# AFE.net
KiCad netlist of a schematic drawn in Altium Designer
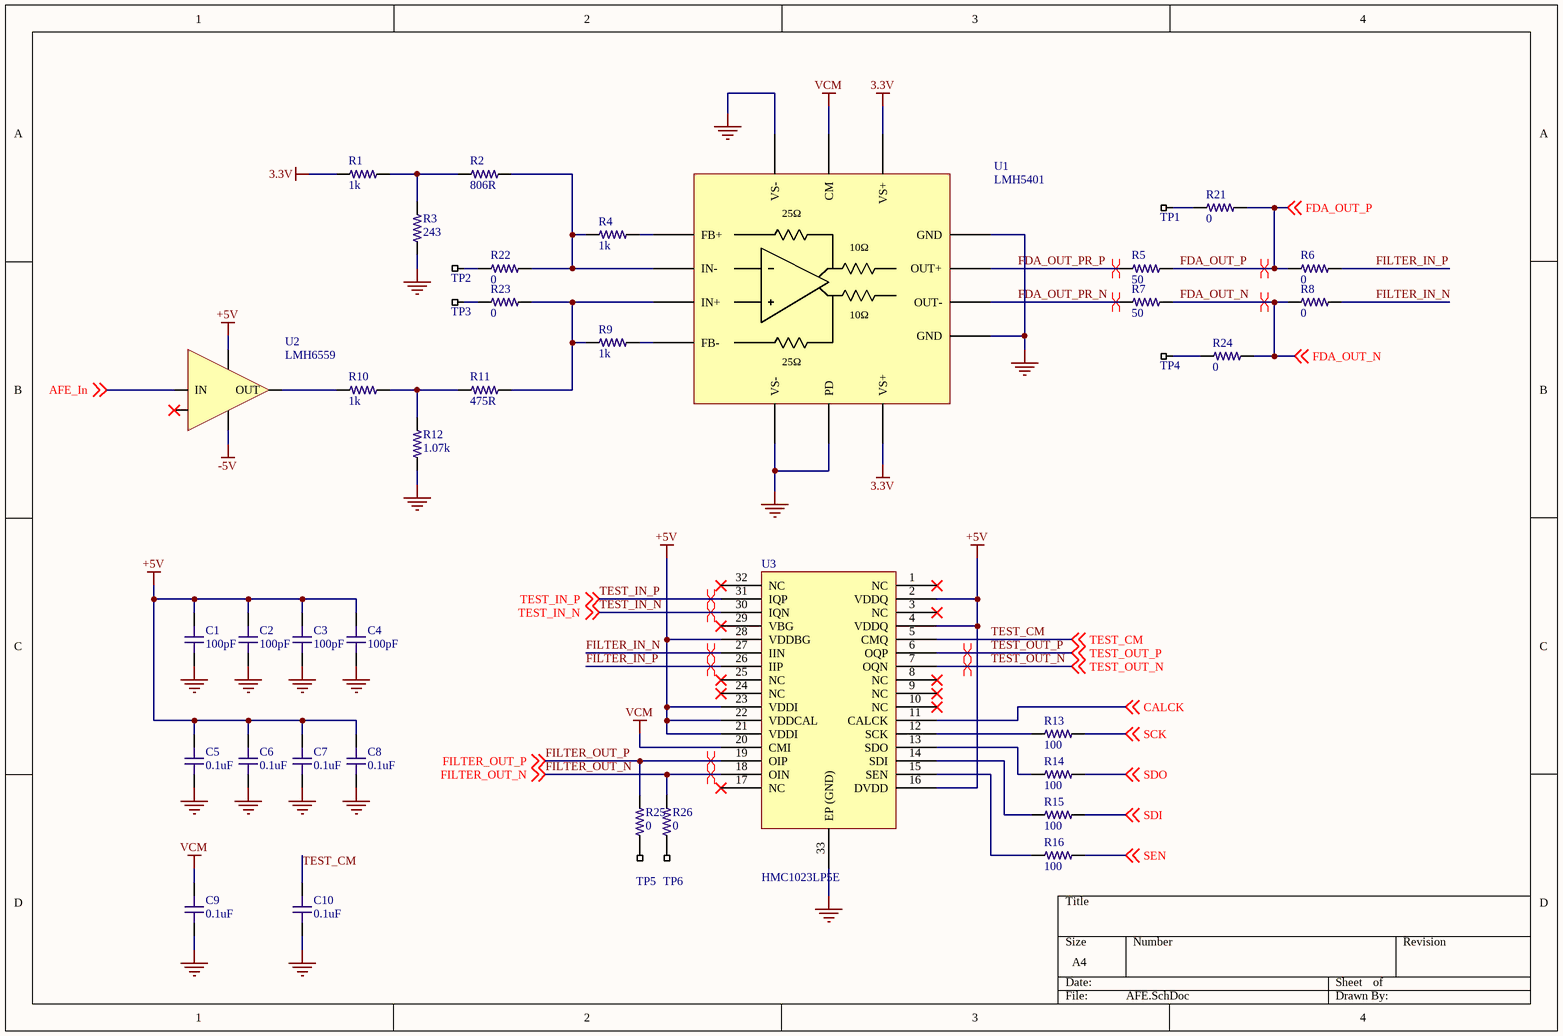
[diagram p0: AFE.SchDoc]

(export (version "E")
  (design (tool "Eeschema 10.0.6"))
  (components
    (comp (ref "C1")
      (value "100pF")
      (footprint "C0402-IPC")
      (description "Chip Capacitor, 0402, 100p, 1%, 50V, C0G")
      (fields (field (name "Comment") "C0402 100pF 50V C0G"))
      (libsource (lib "Capacitors") (part "C0402 100pF 50V C0G"))
    )
    (comp (ref "C2")
      (value "100pF")
      (footprint "C0402-IPC")
      (description "Chip Capacitor, 0402, 100p, 1%, 50V, C0G")
      (fields (field (name "Comment") "C0402 100pF 50V C0G"))
      (libsource (lib "Capacitors") (part "C0402 100pF 50V C0G"))
    )
    (comp (ref "C3")
      (value "100pF")
      (footprint "C0402-IPC")
      (description "Chip Capacitor, 0402, 100p, 1%, 50V, C0G")
      (fields (field (name "Comment") "C0402 100pF 50V C0G"))
      (libsource (lib "Capacitors") (part "C0402 100pF 50V C0G"))
    )
    (comp (ref "C4")
      (value "100pF")
      (footprint "C0402-IPC")
      (description "Chip Capacitor, 0402, 100p, 1%, 50V, C0G")
      (fields (field (name "Comment") "C0402 100pF 50V C0G"))
      (libsource (lib "Capacitors") (part "C0402 100pF 50V C0G"))
    )
    (comp (ref "C5")
      (value "0.1uF")
      (footprint "C0402-HIGH-DENSITY")
      (description "Chip Capacitor, 0402, 0.10uF, 50V, X7R")
      (fields (field (name "Comment") "GRM155R71H104KE14D"))
      (libsource (lib "Capacitors") (part "C0402 0.1uF 50V X7R"))
    )
    (comp (ref "C6")
      (value "0.1uF")
      (footprint "C0402-HIGH-DENSITY")
      (description "Chip Capacitor, 0402, 0.10uF, 50V, X7R")
      (fields (field (name "Comment") "GRM155R71H104KE14D"))
      (libsource (lib "Capacitors") (part "C0402 0.1uF 50V X7R"))
    )
    (comp (ref "C7")
      (value "0.1uF")
      (footprint "C0402-HIGH-DENSITY")
      (description "Chip Capacitor, 0402, 0.10uF, 50V, X7R")
      (fields (field (name "Comment") "GRM155R71H104KE14D"))
      (libsource (lib "Capacitors") (part "C0402 0.1uF 50V X7R"))
    )
    (comp (ref "C8")
      (value "0.1uF")
      (footprint "C0402-HIGH-DENSITY")
      (description "Chip Capacitor, 0402, 0.10uF, 50V, X7R")
      (fields (field (name "Comment") "GRM155R71H104KE14D"))
      (libsource (lib "Capacitors") (part "C0402 0.1uF 50V X7R"))
    )
    (comp (ref "C9")
      (value "0.1uF")
      (footprint "C0402-HIGH-DENSITY")
      (description "Chip Capacitor, 0402, 0.10uF, 50V, X7R")
      (fields (field (name "Comment") "GRM155R71H104KE14D"))
      (libsource (lib "Capacitors") (part "C0402 0.1uF 50V X7R"))
    )
    (comp (ref "C10")
      (value "0.1uF")
      (footprint "C0402-HIGH-DENSITY")
      (description "Chip Capacitor, 0402, 0.10uF, 50V, X7R")
      (fields (field (name "Comment") "GRM155R71H104KE14D"))
      (libsource (lib "Capacitors") (part "C0402 0.1uF 50V X7R"))
    )
    (comp (ref "R1")
      (value "1k")
      (footprint "R0402-HIGH-DENSITY")
      (description "Chip Resistor, 0402, 1k ohms, 1%, 1/16 W")
      (fields (field (name "Comment") "R0402 1k 1%"))
      (libsource (lib "Resistors") (part "R0402 1k 1%"))
    )
    (comp (ref "R2")
      (value "806R")
      (footprint "R0603-HIGH-DENSITY")
      (description "RES 806 OHM 0.5% 1/10W 0603")
      (fields
        (field (name "MANUFACTURER") "Stackpole Electronics")
        (field (name "MANUFACTURER PART NUMBER") "RNCF0603DTE806R")
      )
      (libsource (lib "AFE") (part "806R 0603 0.5% 1/10W"))
    )
    (comp (ref "R3")
      (value "243")
      (footprint "R0603-IPC")
      (description "RES SMD 243 OHM 1% 1/10W 0603")
      (fields (field (name "TOLERANCE") "±1%") (field (name "Comment") "R0603 243 1%"))
      (libsource (lib "Resistors") (part "R0603 243 1%"))
    )
    (comp (ref "R4")
      (value "1k")
      (footprint "R0402-HIGH-DENSITY")
      (description "Chip Resistor, 0402, 1k ohms, 1%, 1/16 W")
      (fields (field (name "Comment") "R0402 1k 1%"))
      (libsource (lib "Resistors") (part "R0402 1k 1%"))
    )
    (comp (ref "R5")
      (value "50")
      (footprint "R0402-HIGH-DENSITY")
      (description "Chip Resistor, 0402, 50 ohms, 1%, 1/10 W")
      (fields (field (name "Comment") "R0402 51 1%"))
      (libsource (lib "Resistors") (part "R0402 51 1%"))
    )
    (comp (ref "R6")
      (value "0")
      (footprint "R0402-HIGH-DENSITY")
      (description "Chip Resistor, 0402, 0 ohm jumper")
      (fields (field (name "Comment") "R0402 0R"))
      (libsource (lib "Resistors") (part "R0402 0R"))
    )
    (comp (ref "R7")
      (value "50")
      (footprint "R0402-HIGH-DENSITY")
      (description "Chip Resistor, 0402, 50 ohms, 1%, 1/10 W")
      (fields (field (name "Comment") "R0402 51 1%"))
      (libsource (lib "Resistors") (part "R0402 51 1%"))
    )
    (comp (ref "R8")
      (value "0")
      (footprint "R0402-HIGH-DENSITY")
      (description "Chip Resistor, 0402, 0 ohm jumper")
      (fields (field (name "Comment") "R0402 0R"))
      (libsource (lib "Resistors") (part "R0402 0R"))
    )
    (comp (ref "R9")
      (value "1k")
      (footprint "R0402-HIGH-DENSITY")
      (description "Chip Resistor, 0402, 1k ohms, 1%, 1/16 W")
      (fields (field (name "Comment") "R0402 1k 1%"))
      (libsource (lib "Resistors") (part "R0402 1k 1%"))
    )
    (comp (ref "R10")
      (value "1k")
      (footprint "R0402-HIGH-DENSITY")
      (description "Chip Resistor, 0402, 1k ohms, 1%, 1/16 W")
      (fields (field (name "Comment") "R0402 1k 1%"))
      (libsource (lib "Resistors") (part "R0402 1k 1%"))
    )
    (comp (ref "R11")
      (value "475R")
      (footprint "R0402-HIGH-DENSITY")
      (description "RES SMD 475 OHM 1% 1/5W 0402")
      (fields
        (field (name "MANUFACTURER") "Vishay Dale")
        (field (name "MANUFACTURER PART NUMBER") "CRCW0402475RFKEDHP")
      )
      (libsource (lib "AFE") (part "475R 0402 1% 1/5W"))
    )
    (comp (ref "R12")
      (value "1.07k")
      (footprint "R0603-HIGH-DENSITY")
      (description "RES SMD 1.07K OHM 1% 1/10W 0603")
      (fields
        (field (name "MANUFACTURER") "Stackpole Electronics")
        (field (name "MANUFACTURER PART NUMBER") "RMCF0603FT1K07")
      )
      (libsource (lib "AFE") (part "1.07k 0603 1% 1/10W"))
    )
    (comp (ref "R13")
      (value "100")
      (footprint "R0402-HIGH-DENSITY")
      (description "Chip Resistor, 0402, 100 ohms, 1%, 1/16 W")
      (fields (field (name "Comment") "R0402 100R 1%"))
      (libsource (lib "Resistors") (part "R0402 100R 1%"))
    )
    (comp (ref "R14")
      (value "100")
      (footprint "R0402-HIGH-DENSITY")
      (description "Chip Resistor, 0402, 100 ohms, 1%, 1/16 W")
      (fields (field (name "Comment") "R0402 100R 1%"))
      (libsource (lib "Resistors") (part "R0402 100R 1%"))
    )
    (comp (ref "R15")
      (value "100")
      (footprint "R0402-HIGH-DENSITY")
      (description "Chip Resistor, 0402, 100 ohms, 1%, 1/16 W")
      (fields (field (name "Comment") "R0402 100R 1%"))
      (libsource (lib "Resistors") (part "R0402 100R 1%"))
    )
    (comp (ref "R16")
      (value "100")
      (footprint "R0402-HIGH-DENSITY")
      (description "Chip Resistor, 0402, 100 ohms, 1%, 1/16 W")
      (fields (field (name "Comment") "R0402 100R 1%"))
      (libsource (lib "Resistors") (part "R0402 100R 1%"))
    )
    (comp (ref "R21")
      (value "0")
      (footprint "R0402-HIGH-DENSITY")
      (description "Chip Resistor, 0402, 0 ohm jumper")
      (fields (field (name "Comment") "R0402 0R"))
      (libsource (lib "AFE") (part "R0402 0R"))
    )
    (comp (ref "R22")
      (value "0")
      (footprint "R0402-HIGH-DENSITY")
      (description "Chip Resistor, 0402, 0 ohm jumper")
      (fields (field (name "Comment") "R0402 0R"))
      (libsource (lib "AFE") (part "R0402 0R"))
    )
    (comp (ref "R23")
      (value "0")
      (footprint "R0402-HIGH-DENSITY")
      (description "Chip Resistor, 0402, 0 ohm jumper")
      (fields (field (name "Comment") "R0402 0R"))
      (libsource (lib "AFE") (part "R0402 0R"))
    )
    (comp (ref "R24")
      (value "0")
      (footprint "R0402-HIGH-DENSITY")
      (description "Chip Resistor, 0402, 0 ohm jumper")
      (fields (field (name "Comment") "R0402 0R"))
      (libsource (lib "AFE") (part "R0402 0R"))
    )
    (comp (ref "R25")
      (value "0")
      (footprint "R0402-HIGH-DENSITY")
      (description "Chip Resistor, 0402, 0 ohm jumper")
      (fields (field (name "Comment") "R0402 0R"))
      (libsource (lib "AFE") (part "R0402 0R"))
    )
    (comp (ref "R26")
      (value "0")
      (footprint "R0402-HIGH-DENSITY")
      (description "Chip Resistor, 0402, 0 ohm jumper")
      (fields (field (name "Comment") "R0402 0R"))
      (libsource (lib "AFE") (part "R0402 0R"))
    )
    (comp (ref "TP1")
      (value "Testpoint_SMT")
      (footprint "TESTPOINT_SMT")
      (description "SMT Test Point")
      (libsource (lib "Virtual Parts") (part "Testpoint_SMT"))
    )
    (comp (ref "TP2")
      (value "Testpoint_SMT")
      (footprint "TESTPOINT_SMT")
      (description "SMT Test Point")
      (libsource (lib "Virtual Parts") (part "Testpoint_SMT"))
    )
    (comp (ref "TP3")
      (value "Testpoint_SMT")
      (footprint "TESTPOINT_SMT")
      (description "SMT Test Point")
      (libsource (lib "Virtual Parts") (part "Testpoint_SMT"))
    )
    (comp (ref "TP4")
      (value "Testpoint_SMT")
      (footprint "TESTPOINT_SMT")
      (description "SMT Test Point")
      (libsource (lib "Virtual Parts") (part "Testpoint_SMT"))
    )
    (comp (ref "TP5")
      (value "Testpoint_SMT")
      (footprint "TESTPOINT_SMT")
      (description "SMT Test Point")
      (libsource (lib "Virtual Parts") (part "Testpoint_SMT"))
    )
    (comp (ref "TP6")
      (value "Testpoint_SMT")
      (footprint "TESTPOINT_SMT")
      (description "SMT Test Point")
      (libsource (lib "Virtual Parts") (part "Testpoint_SMT"))
    )
    (comp (ref "U1")
      (value "LMH5401")
      (footprint "LMH5401")
      (description "TEXAS INSTRUMENTS - LMH5401IRMST - DIFF AMP, 6.2GHZ, 17.5KV/US, UQFN-14")
      (fields
        (field (name "MANUFACTURER") "Texas Instruments")
        (field (name "MANUFACTURER PART NUMBER") "LMH5401IRMST")
      )
      (libsource (lib "AFE") (part "LMH5401"))
    )
    (comp (ref "U2")
      (value "LMH6559")
      (footprint "LMH6559")
      (description "OP Amp Buffer Single GP 10V 5-Pin SOT-23 T/R")
      (fields
        (field (name "MANUFACTURER") "TI National Semiconductor")
        (field (name "MANUFACTURER PART NUMBER") "LMH6559MF/NOPB")
      )
      (libsource (lib "AFE") (part "LMH6559"))
    )
    (comp (ref "U3")
      (value "HMC1023LP5E")
      (footprint "HMC1023")
      (description "Active Filter Dual Low Pass Filter 6th Order 72MHz 32-Pin QFN Bulk")
      (fields (field (name "MANUFACTURER") "Analog Devices"))
      (libsource (lib "AFE") (part "HMC1023LP5E"))
    )
  )
  (nets
    (net (code "1") (name "+5V") (class "Default")
      (node (ref "C1") (pin "2") (pintype "passive"))
      (node (ref "C2") (pin "2") (pintype "passive"))
      (node (ref "C3") (pin "2") (pintype "passive"))
      (node (ref "C4") (pin "2") (pintype "passive"))
      (node (ref "C5") (pin "2") (pintype "passive"))
      (node (ref "C6") (pin "2") (pintype "passive"))
      (node (ref "C7") (pin "2") (pintype "passive"))
      (node (ref "C8") (pin "2") (pintype "passive"))
      (node (ref "U2") (pin "5") (pinfunction "V+_5") (pintype "passive"))
      (node (ref "U3") (pin "16") (pinfunction "DVDD_16") (pintype "passive"))
      (node (ref "U3") (pin "2") (pinfunction "VDDQ_2") (pintype "passive"))
      (node (ref "U3") (pin "21") (pinfunction "VDDI_21") (pintype "passive"))
      (node (ref "U3") (pin "22") (pinfunction "VDDCAL_22") (pintype "passive"))
      (node (ref "U3") (pin "23") (pinfunction "VDDI_23") (pintype "passive"))
      (node (ref "U3") (pin "28") (pinfunction "VDDBG_28") (pintype "passive"))
      (node (ref "U3") (pin "4") (pinfunction "VDDQ_4") (pintype "passive"))
    )
    (net (code "2") (name "-5V") (class "Default")
      (node (ref "U2") (pin "2") (pinfunction "V-_2") (pintype "passive"))
    )
    (net (code "3") (name "/FDA_OUT_PR_N") (class "Default")
      (node (ref "R7") (pin "1") (pintype "passive"))
      (node (ref "U1") (pin "12") (pinfunction "OUT-_12") (pintype "passive"))
    )
    (net (code "4") (name "/FDA_OUT_PR_P") (class "Default")
      (node (ref "R5") (pin "1") (pintype "passive"))
      (node (ref "U1") (pin "13") (pinfunction "OUT+_13") (pintype "passive"))
    )
    (net (code "5") (name "/FILTER_IN_N") (class "Default")
      (node (ref "R8") (pin "2") (pintype "passive"))
      (node (ref "U3") (pin "27") (pinfunction "IIN_27") (pintype "passive"))
    )
    (net (code "6") (name "/FILTER_IN_P") (class "Default")
      (node (ref "R6") (pin "2") (pintype "passive"))
      (node (ref "U3") (pin "26") (pinfunction "IIP_26") (pintype "passive"))
    )
    (net (code "7") (name "3.3V") (class "Default")
      (node (ref "R1") (pin "1") (pintype "passive"))
      (node (ref "U1") (pin "1") (pinfunction "VS+_1") (pintype "passive"))
      (node (ref "U1") (pin "10") (pinfunction "VS+_10") (pintype "passive"))
    )
    (net (code "8") (name "AFE_In") (class "Default")
      (node (ref "U2") (pin "4") (pinfunction "IN_4") (pintype "passive"))
    )
    (net (code "9") (name "CALCK") (class "Default")
      (node (ref "U3") (pin "11") (pinfunction "CALCK_11") (pintype "passive"))
    )
    (net (code "10") (name "FDA_OUT_N") (class "Default")
      (node (ref "R24") (pin "2") (pintype "passive"))
      (node (ref "R7") (pin "2") (pintype "passive"))
      (node (ref "R8") (pin "1") (pintype "passive"))
    )
    (net (code "11") (name "FDA_OUT_P") (class "Default")
      (node (ref "R21") (pin "2") (pintype "passive"))
      (node (ref "R5") (pin "2") (pintype "passive"))
      (node (ref "R6") (pin "1") (pintype "passive"))
    )
    (net (code "12") (name "FILTER_OUT_N") (class "Default")
      (node (ref "R26") (pin "2") (pintype "passive"))
      (node (ref "U3") (pin "18") (pinfunction "OIN_18") (pintype "passive"))
    )
    (net (code "13") (name "FILTER_OUT_P") (class "Default")
      (node (ref "R25") (pin "2") (pintype "passive"))
      (node (ref "U3") (pin "19") (pinfunction "OIP_19") (pintype "passive"))
    )
    (net (code "14") (name "GND") (class "Default")
      (node (ref "C1") (pin "1") (pintype "passive"))
      (node (ref "C10") (pin "1") (pintype "passive"))
      (node (ref "C2") (pin "1") (pintype "passive"))
      (node (ref "C3") (pin "1") (pintype "passive"))
      (node (ref "C4") (pin "1") (pintype "passive"))
      (node (ref "C5") (pin "1") (pintype "passive"))
      (node (ref "C6") (pin "1") (pintype "passive"))
      (node (ref "C7") (pin "1") (pintype "passive"))
      (node (ref "C8") (pin "1") (pintype "passive"))
      (node (ref "C9") (pin "1") (pintype "passive"))
      (node (ref "R12") (pin "1") (pintype "passive"))
      (node (ref "R3") (pin "1") (pintype "passive"))
      (node (ref "U1") (pin "11") (pinfunction "GND_11") (pintype "passive"))
      (node (ref "U1") (pin "14") (pinfunction "GND_14") (pintype "passive"))
      (node (ref "U1") (pin "3") (pinfunction "VS-_3") (pintype "passive"))
      (node (ref "U1") (pin "8") (pinfunction "VS-_8") (pintype "passive"))
      (node (ref "U1") (pin "9") (pinfunction "PD_9") (pintype "passive"))
      (node (ref "U3") (pin "33") (pinfunction "EP_(GND)_33") (pintype "passive"))
    )
    (net (code "15") (name "Net-(R1-Pad2)") (class "Default")
      (node (ref "R1") (pin "2") (pintype "passive"))
      (node (ref "R2") (pin "1") (pintype "passive"))
      (node (ref "R3") (pin "2") (pintype "passive"))
    )
    (net (code "16") (name "Net-(R10-Pad2)") (class "Default")
      (node (ref "R10") (pin "2") (pintype "passive"))
      (node (ref "R11") (pin "1") (pintype "passive"))
      (node (ref "R12") (pin "2") (pintype "passive"))
    )
    (net (code "17") (name "Net-(R21-Pad1)") (class "Default")
      (node (ref "R21") (pin "1") (pintype "passive"))
      (node (ref "TP1") (pin "1") (pinfunction "1_1") (pintype "passive"))
    )
    (net (code "18") (name "Net-(R22-Pad1)") (class "Default")
      (node (ref "R22") (pin "1") (pintype "passive"))
      (node (ref "TP2") (pin "1") (pinfunction "1_1") (pintype "passive"))
    )
    (net (code "19") (name "Net-(R23-Pad1)") (class "Default")
      (node (ref "R23") (pin "1") (pintype "passive"))
      (node (ref "TP3") (pin "1") (pinfunction "1_1") (pintype "passive"))
    )
    (net (code "20") (name "Net-(R24-Pad1)") (class "Default")
      (node (ref "R24") (pin "1") (pintype "passive"))
      (node (ref "TP4") (pin "1") (pinfunction "1_1") (pintype "passive"))
    )
    (net (code "21") (name "Net-(R25-Pad1)") (class "Default")
      (node (ref "R25") (pin "1") (pintype "passive"))
      (node (ref "TP5") (pin "1") (pinfunction "1_1") (pintype "passive"))
    )
    (net (code "22") (name "Net-(R26-Pad1)") (class "Default")
      (node (ref "R26") (pin "1") (pintype "passive"))
      (node (ref "TP6") (pin "1") (pinfunction "1_1") (pintype "passive"))
    )
    (net (code "23") (name "Net-(U1-FB+)") (class "Default")
      (node (ref "R4") (pin "2") (pintype "passive"))
      (node (ref "U1") (pin "4") (pinfunction "FB+_4") (pintype "passive"))
    )
    (net (code "24") (name "Net-(U1-FB-)") (class "Default")
      (node (ref "R9") (pin "2") (pintype "passive"))
      (node (ref "U1") (pin "7") (pinfunction "FB-_7") (pintype "passive"))
    )
    (net (code "25") (name "Net-(U1-IN+)") (class "Default")
      (node (ref "R11") (pin "2") (pintype "passive"))
      (node (ref "R23") (pin "2") (pintype "passive"))
      (node (ref "R9") (pin "1") (pintype "passive"))
      (node (ref "U1") (pin "6") (pinfunction "IN+_6") (pintype "passive"))
    )
    (net (code "26") (name "Net-(U1-IN-)") (class "Default")
      (node (ref "R2") (pin "2") (pintype "passive"))
      (node (ref "R22") (pin "2") (pintype "passive"))
      (node (ref "R4") (pin "1") (pintype "passive"))
      (node (ref "U1") (pin "5") (pinfunction "IN-_5") (pintype "passive"))
    )
    (net (code "27") (name "Net-(U2-OUT)") (class "Default")
      (node (ref "R10") (pin "1") (pintype "passive"))
      (node (ref "U2") (pin "1") (pinfunction "OUT_1") (pintype "passive"))
    )
    (net (code "28") (name "Net-(U3-SCK)") (class "Default")
      (node (ref "R13") (pin "1") (pintype "passive"))
      (node (ref "U3") (pin "12") (pinfunction "SCK_12") (pintype "passive"))
    )
    (net (code "29") (name "Net-(U3-SDI)") (class "Default")
      (node (ref "R15") (pin "1") (pintype "passive"))
      (node (ref "U3") (pin "14") (pinfunction "SDI_14") (pintype "passive"))
    )
    (net (code "30") (name "Net-(U3-SDO)") (class "Default")
      (node (ref "R14") (pin "1") (pintype "passive"))
      (node (ref "U3") (pin "13") (pinfunction "SDO_13") (pintype "passive"))
    )
    (net (code "31") (name "Net-(U3-SEN)") (class "Default")
      (node (ref "R16") (pin "1") (pintype "passive"))
      (node (ref "U3") (pin "15") (pinfunction "SEN_15") (pintype "passive"))
    )
    (net (code "32") (name "SCK") (class "Default") (node (ref "R13") (pin "2") (pintype "passive")))
    (net (code "33") (name "SDI") (class "Default") (node (ref "R15") (pin "2") (pintype "passive")))
    (net (code "34") (name "SDO") (class "Default") (node (ref "R14") (pin "2") (pintype "passive")))
    (net (code "35") (name "SEN") (class "Default") (node (ref "R16") (pin "2") (pintype "passive")))
    (net (code "36") (name "TEST_CM") (class "Default")
      (node (ref "C10") (pin "2") (pintype "passive"))
      (node (ref "U3") (pin "5") (pinfunction "CMQ_5") (pintype "passive"))
    )
    (net (code "37") (name "TEST_IN_N") (class "Default")
      (node (ref "U3") (pin "30") (pinfunction "IQN_30") (pintype "passive"))
    )
    (net (code "38") (name "TEST_IN_P") (class "Default")
      (node (ref "U3") (pin "31") (pinfunction "IQP_31") (pintype "passive"))
    )
    (net (code "39") (name "TEST_OUT_N") (class "Default")
      (node (ref "U3") (pin "7") (pinfunction "OQN_7") (pintype "passive"))
    )
    (net (code "40") (name "TEST_OUT_P") (class "Default")
      (node (ref "U3") (pin "6") (pinfunction "OQP_6") (pintype "passive"))
    )
    (net (code "41") (name "VCM") (class "Default")
      (node (ref "C9") (pin "2") (pintype "passive"))
      (node (ref "U1") (pin "2") (pinfunction "CM_2") (pintype "passive"))
      (node (ref "U3") (pin "20") (pinfunction "CMI_20") (pintype "passive"))
    )
    (net (code "42") (name "unconnected-(U2-NC-Pad3)") (class "Default")
      (node (ref "U2") (pin "3") (pinfunction "NC_3") (pintype "passive+no_connect"))
    )
    (net (code "43") (name "unconnected-(U3-NC-Pad1)") (class "Default")
      (node (ref "U3") (pin "1") (pinfunction "NC_1") (pintype "passive+no_connect"))
    )
    (net (code "44") (name "unconnected-(U3-NC-Pad3)") (class "Default")
      (node (ref "U3") (pin "3") (pinfunction "NC_3") (pintype "passive+no_connect"))
    )
    (net (code "45") (name "unconnected-(U3-NC-Pad8)") (class "Default")
      (node (ref "U3") (pin "8") (pinfunction "NC_8") (pintype "passive+no_connect"))
    )
    (net (code "46") (name "unconnected-(U3-NC-Pad9)") (class "Default")
      (node (ref "U3") (pin "9") (pinfunction "NC_9") (pintype "passive+no_connect"))
    )
    (net (code "47") (name "unconnected-(U3-NC-Pad10)") (class "Default")
      (node (ref "U3") (pin "10") (pinfunction "NC_10") (pintype "passive+no_connect"))
    )
    (net (code "48") (name "unconnected-(U3-NC-Pad17)") (class "Default")
      (node (ref "U3") (pin "17") (pinfunction "NC_17") (pintype "passive+no_connect"))
    )
    (net (code "49") (name "unconnected-(U3-NC-Pad24)") (class "Default")
      (node (ref "U3") (pin "24") (pinfunction "NC_24") (pintype "passive+no_connect"))
    )
    (net (code "50") (name "unconnected-(U3-NC-Pad25)") (class "Default")
      (node (ref "U3") (pin "25") (pinfunction "NC_25") (pintype "passive+no_connect"))
    )
    (net (code "51") (name "unconnected-(U3-NC-Pad32)") (class "Default")
      (node (ref "U3") (pin "32") (pinfunction "NC_32") (pintype "passive+no_connect"))
    )
    (net (code "52") (name "unconnected-(U3-VBG-Pad29)") (class "Default")
      (node (ref "U3") (pin "29") (pinfunction "VBG_29") (pintype "passive+no_connect"))
    )
  )
)
